# RoBeast_DC_Brake.net
KiCad netlist of a schematic drawn in Altium Designer
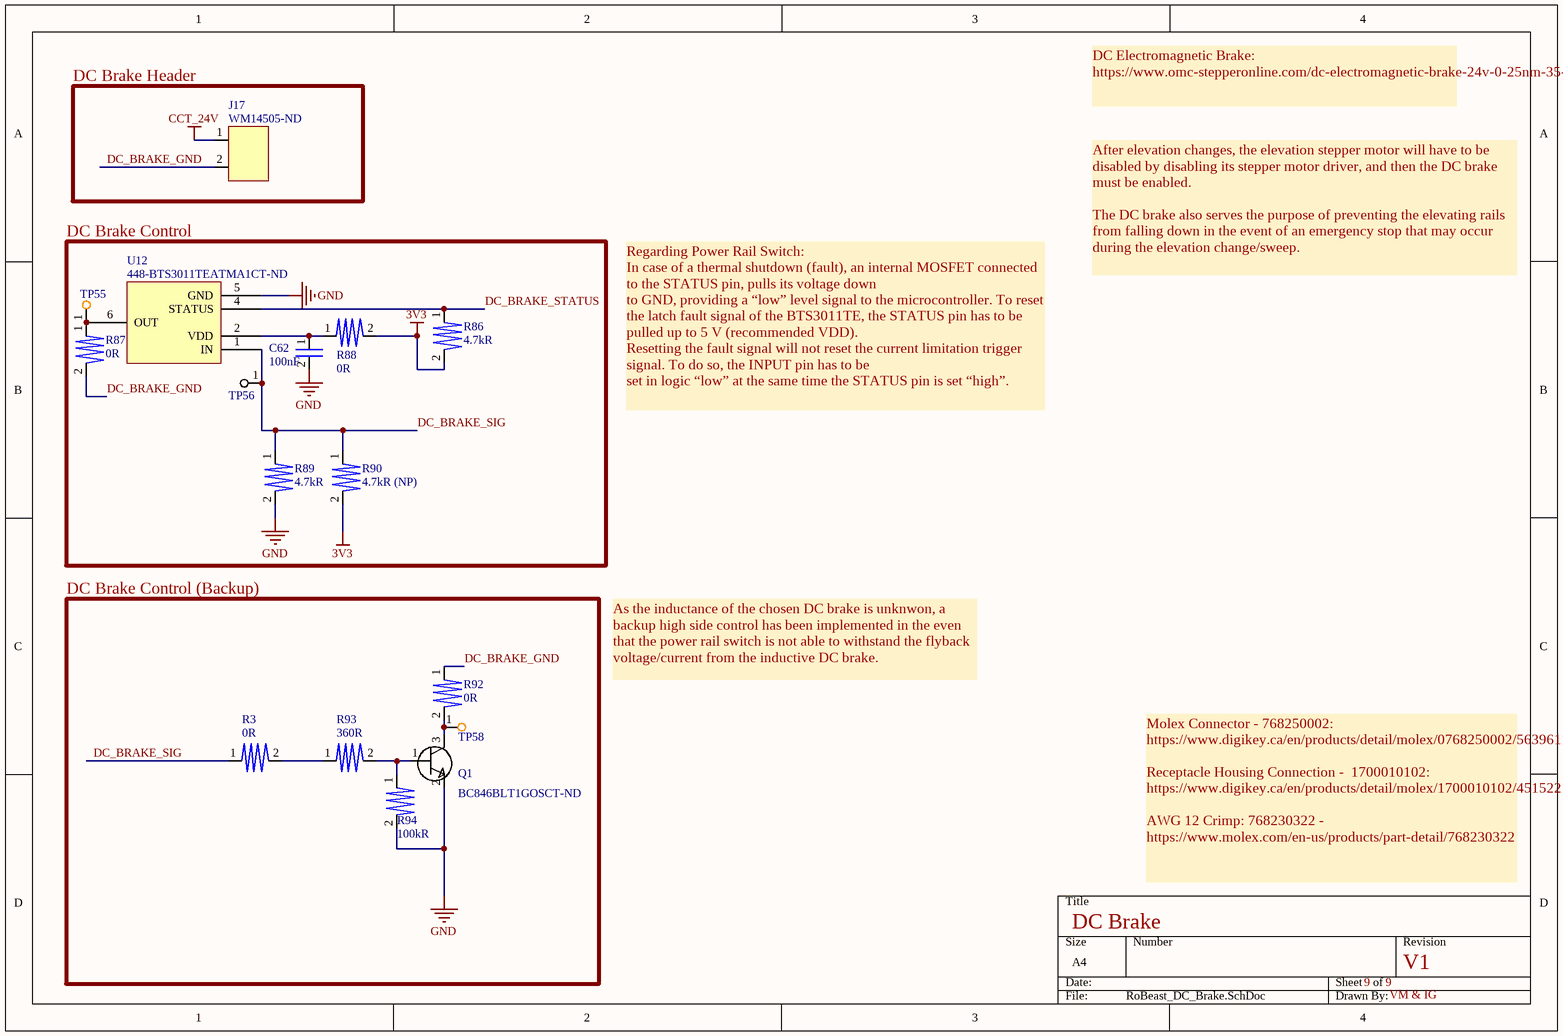
[diagram p0: RoBeast_DC_Brake.SchDoc]

(export (version "E")
  (design (tool "Eeschema 10.0.6"))
  (components
    (comp (ref "C62")
      (value "100nF")
      (footprint "0805")
      (fields
        (field (name "MANUFACTURER") "KEMET")
        (field (name "MANUFACTURER PART NUMBER") "C0805C104J5RACTU")
      )
      (libsource (lib "RoBeast_Schematic_Library") (part "C0805C104J5RAC7800"))
    )
    (comp (ref "J17")
      (value "2 Pin Connector")
      (footprint "WM14505-ND")
      (description "Board Connector, 2 Contact(s), 2 Row(s), Male, Right Angle, Solder Terminal")
      (fields
        (field (name "MANUFACTURER") "Molex")
        (field (name "MANUFACTURER PART NUMBER") "0026013114")
        (field (name "SUPPLIER PART NUMBER 1") "WM14505-ND")
      )
      (libsource (lib "RoBeast_Schematic_Library") (part "WM14505-ND"))
    )
    (comp (ref "Q1")
      (value "NPN BJT")
      (footprint "BC846BLT1G")
      (description "Small Signal Bipolar Transistor, 0.1A I(C), 65V V(BR)CEO, 1-Element, NPN, Silicon, TO-236")
      (fields
        (field (name "MANUFACTURER") "ON Semiconductor")
        (field (name "MANUFACTURER PART NUMBER") "BC846BLT1G")
        (field (name "SUPPLIER PART NUMBER 1") "BC846BLT1GOSCT-ND")
      )
      (libsource (lib "RoBeast_Schematic_Library") (part "BC846BLT1G"))
    )
    (comp (ref "R3")
      (value "0R")
      (footprint "0805")
      (description "Fixed Resistor, Metal Glaze/thick Film, 0.125W, 0ohm, Surface Mount, 0805")
      (fields
        (field (name "MANUFACTURER") "Stackpole Electronics")
        (field (name "MANUFACTURER PART NUMBER") "RMCF0805ZT0R00")
      )
      (libsource (lib "RoBeast_Schematic_Library") (part "RMCF0805ZT0R00"))
    )
    (comp (ref "R86")
      (value "4.7kR")
      (footprint "0805")
      (fields
        (field (name "MANUFACTURER") "Vishay Dale")
        (field (name "MANUFACTURER PART NUMBER") "RCC08054K70FKEA")
      )
      (libsource (lib "RoBeast_Schematic_Library") (part "RCC08054K70FKEA"))
    )
    (comp (ref "R87")
      (value "0R")
      (footprint "0805")
      (description "Fixed Resistor, Metal Glaze/thick Film, 0.125W, 0ohm, Surface Mount, 0805")
      (fields
        (field (name "MANUFACTURER") "Stackpole Electronics")
        (field (name "MANUFACTURER PART NUMBER") "RMCF0805ZT0R00")
      )
      (libsource (lib "RoBeast_Schematic_Library") (part "RMCF0805ZT0R00"))
    )
    (comp (ref "R88")
      (value "0R")
      (footprint "0805")
      (description "Fixed Resistor, Metal Glaze/thick Film, 0.125W, 0ohm, Surface Mount, 0805")
      (fields
        (field (name "MANUFACTURER") "Stackpole Electronics")
        (field (name "MANUFACTURER PART NUMBER") "RMCF0805ZT0R00")
      )
      (libsource (lib "RoBeast_Schematic_Library") (part "RMCF0805ZT0R00"))
    )
    (comp (ref "R89")
      (value "4.7kR")
      (footprint "0805")
      (fields
        (field (name "MANUFACTURER") "Vishay Dale")
        (field (name "MANUFACTURER PART NUMBER") "RCC08054K70FKEA")
      )
      (libsource (lib "RoBeast_Schematic_Library") (part "RCC08054K70FKEA"))
    )
    (comp (ref "R90")
      (value "4.7kR (NP)")
      (footprint "0805")
      (fields
        (field (name "MANUFACTURER") "Vishay Dale")
        (field (name "MANUFACTURER PART NUMBER") "RCC08054K70FKEA")
      )
      (libsource (lib "RoBeast_Schematic_Library") (part "RCC08054K70FKEA"))
    )
    (comp (ref "R92")
      (value "0R")
      (footprint "0805")
      (description "Fixed Resistor, Metal Glaze/thick Film, 0.125W, 0ohm, Surface Mount, 0805")
      (fields
        (field (name "MANUFACTURER") "Stackpole Electronics")
        (field (name "MANUFACTURER PART NUMBER") "RMCF0805ZT0R00")
      )
      (libsource (lib "RoBeast_Schematic_Library") (part "RMCF0805ZT0R00"))
    )
    (comp (ref "R93")
      (value "360R")
      (footprint "0805")
      (fields
        (field (name "MANUFACTURER") "Yageo")
        (field (name "MANUFACTURER PART NUMBER") "RC0805FR-07360RL")
        (field (name "TOLERANCE") "1%")
      )
      (libsource (lib "RoBeast_Schematic_Library") (part "RC0805FR-07360RL"))
    )
    (comp (ref "R94")
      (value "100kR")
      (footprint "0805")
      (fields
        (field (name "MANUFACTURER") "Vishay")
        (field (name "MANUFACTURER PART NUMBER") "CRCW0805100KFKEAHP")
        (field (name "TOLERANCE") "1%")
      )
      (libsource (lib "RoBeast_Schematic_Library") (part "CRCW0805100KFKEAHP"))
    )
    (comp (ref "TP55")
      (value "Test Point")
      (footprint "Test Point")
      (libsource (lib "RoBeast_Schematic_Library") (part "Test Point"))
    )
    (comp (ref "TP56")
      (value "Test Point")
      (footprint "RCWCTE")
      (description "Testing/Accessories")
      (fields (field (name "MANUFACTURER") "KOA Speer") (field (name "MANUFACTURER PART NUMBER") "RCWCTE"))
      (libsource (lib "RoBeast_Schematic_Library") (part "RCWCTE"))
    )
    (comp (ref "TP58")
      (value "Test Point")
      (footprint "Test Point")
      (libsource (lib "RoBeast_Schematic_Library") (part "Test Point"))
    )
    (comp (ref "U12")
      (value "Power Rail Switch")
      (footprint "BTS3011TEATMA1")
      (description "Current Limit SW 1-IN 1-OUT 3V to 5.5V 10A Automotive 7-Pin(6+Tab) D2PAK T/R")
      (fields
        (field (name "MANUFACTURER") "Infineon")
        (field (name "MANUFACTURER PART NUMBER") "BTS3011TEATMA1")
        (field (name "SUPPLIER PART NUMBER 1") "448-BTS3011TEATMA1CT-ND")
      )
      (libsource (lib "RoBeast_Schematic_Library") (part "BTS3011TEATMA1"))
    )
  )
  (nets
    (net (code "1") (name "/DC_BRAKE_GND") (class "Default")
      (node (ref "J17") (pin "2") (pinfunction "2_2") (pintype "passive"))
      (node (ref "R87") (pin "2") (pinfunction "2_2") (pintype "passive"))
      (node (ref "R92") (pin "1") (pinfunction "1_1") (pintype "passive"))
    )
    (net (code "2") (name "/DC_BRAKE_SIG") (class "Default")
      (node (ref "R3") (pin "1") (pinfunction "1_1") (pintype "passive"))
      (node (ref "R89") (pin "1") (pinfunction "1_1") (pintype "passive"))
      (node (ref "R90") (pin "1") (pinfunction "1_1") (pintype "passive"))
      (node (ref "TP56") (pin "1") (pinfunction "1_1") (pintype "passive"))
      (node (ref "U12") (pin "1") (pinfunction "IN_1") (pintype "passive"))
    )
    (net (code "3") (name "/DC_BRAKE_STATUS") (class "Default")
      (node (ref "R86") (pin "1") (pinfunction "1_1") (pintype "passive"))
      (node (ref "U12") (pin "4") (pinfunction "STATUS_4") (pintype "passive"))
    )
    (net (code "4") (name "3V3") (class "Default")
      (node (ref "R86") (pin "2") (pinfunction "2_2") (pintype "passive"))
      (node (ref "R88") (pin "2") (pinfunction "2_2") (pintype "passive"))
      (node (ref "R90") (pin "2") (pinfunction "2_2") (pintype "passive"))
    )
    (net (code "5") (name "CCT_24V") (class "Default")
      (node (ref "J17") (pin "1") (pinfunction "1_1") (pintype "passive"))
    )
    (net (code "6") (name "GND") (class "Default")
      (node (ref "C62") (pin "2") (pinfunction "2_2") (pintype "passive"))
      (node (ref "Q1") (pin "2") (pinfunction "E_2") (pintype "passive"))
      (node (ref "R89") (pin "2") (pinfunction "2_2") (pintype "passive"))
      (node (ref "R94") (pin "2") (pinfunction "2_2") (pintype "passive"))
      (node (ref "U12") (pin "5") (pinfunction "GND_5") (pintype "passive"))
    )
    (net (code "7") (name "Net-(Q1-B)") (class "Default")
      (node (ref "Q1") (pin "1") (pinfunction "B_1") (pintype "passive"))
      (node (ref "R93") (pin "2") (pinfunction "2_2") (pintype "passive"))
      (node (ref "R94") (pin "1") (pinfunction "1_1") (pintype "passive"))
    )
    (net (code "8") (name "Net-(Q1-C)") (class "Default")
      (node (ref "Q1") (pin "3") (pinfunction "C_3") (pintype "passive"))
      (node (ref "R92") (pin "2") (pinfunction "2_2") (pintype "passive"))
      (node (ref "TP58") (pin "1") (pinfunction "1_1") (pintype "passive"))
    )
    (net (code "9") (name "Net-(R3-Pad2)") (class "Default")
      (node (ref "R3") (pin "2") (pinfunction "2_2") (pintype "passive"))
      (node (ref "R93") (pin "1") (pinfunction "1_1") (pintype "passive"))
    )
    (net (code "10") (name "Net-(U12-OUT)") (class "Default")
      (node (ref "R87") (pin "1") (pinfunction "1_1") (pintype "passive"))
      (node (ref "TP55") (pin "1") (pinfunction "1_1") (pintype "passive"))
      (node (ref "U12") (pin "6") (pinfunction "OUT_6") (pintype "passive"))
    )
    (net (code "11") (name "Net-(U12-VDD)") (class "Default")
      (node (ref "C62") (pin "1") (pinfunction "1_1") (pintype "passive"))
      (node (ref "R88") (pin "1") (pinfunction "1_1") (pintype "passive"))
      (node (ref "U12") (pin "2") (pinfunction "VDD_2") (pintype "passive"))
    )
  )
)
